# switches.net
KiCad netlist of a schematic drawn in Altium Designer
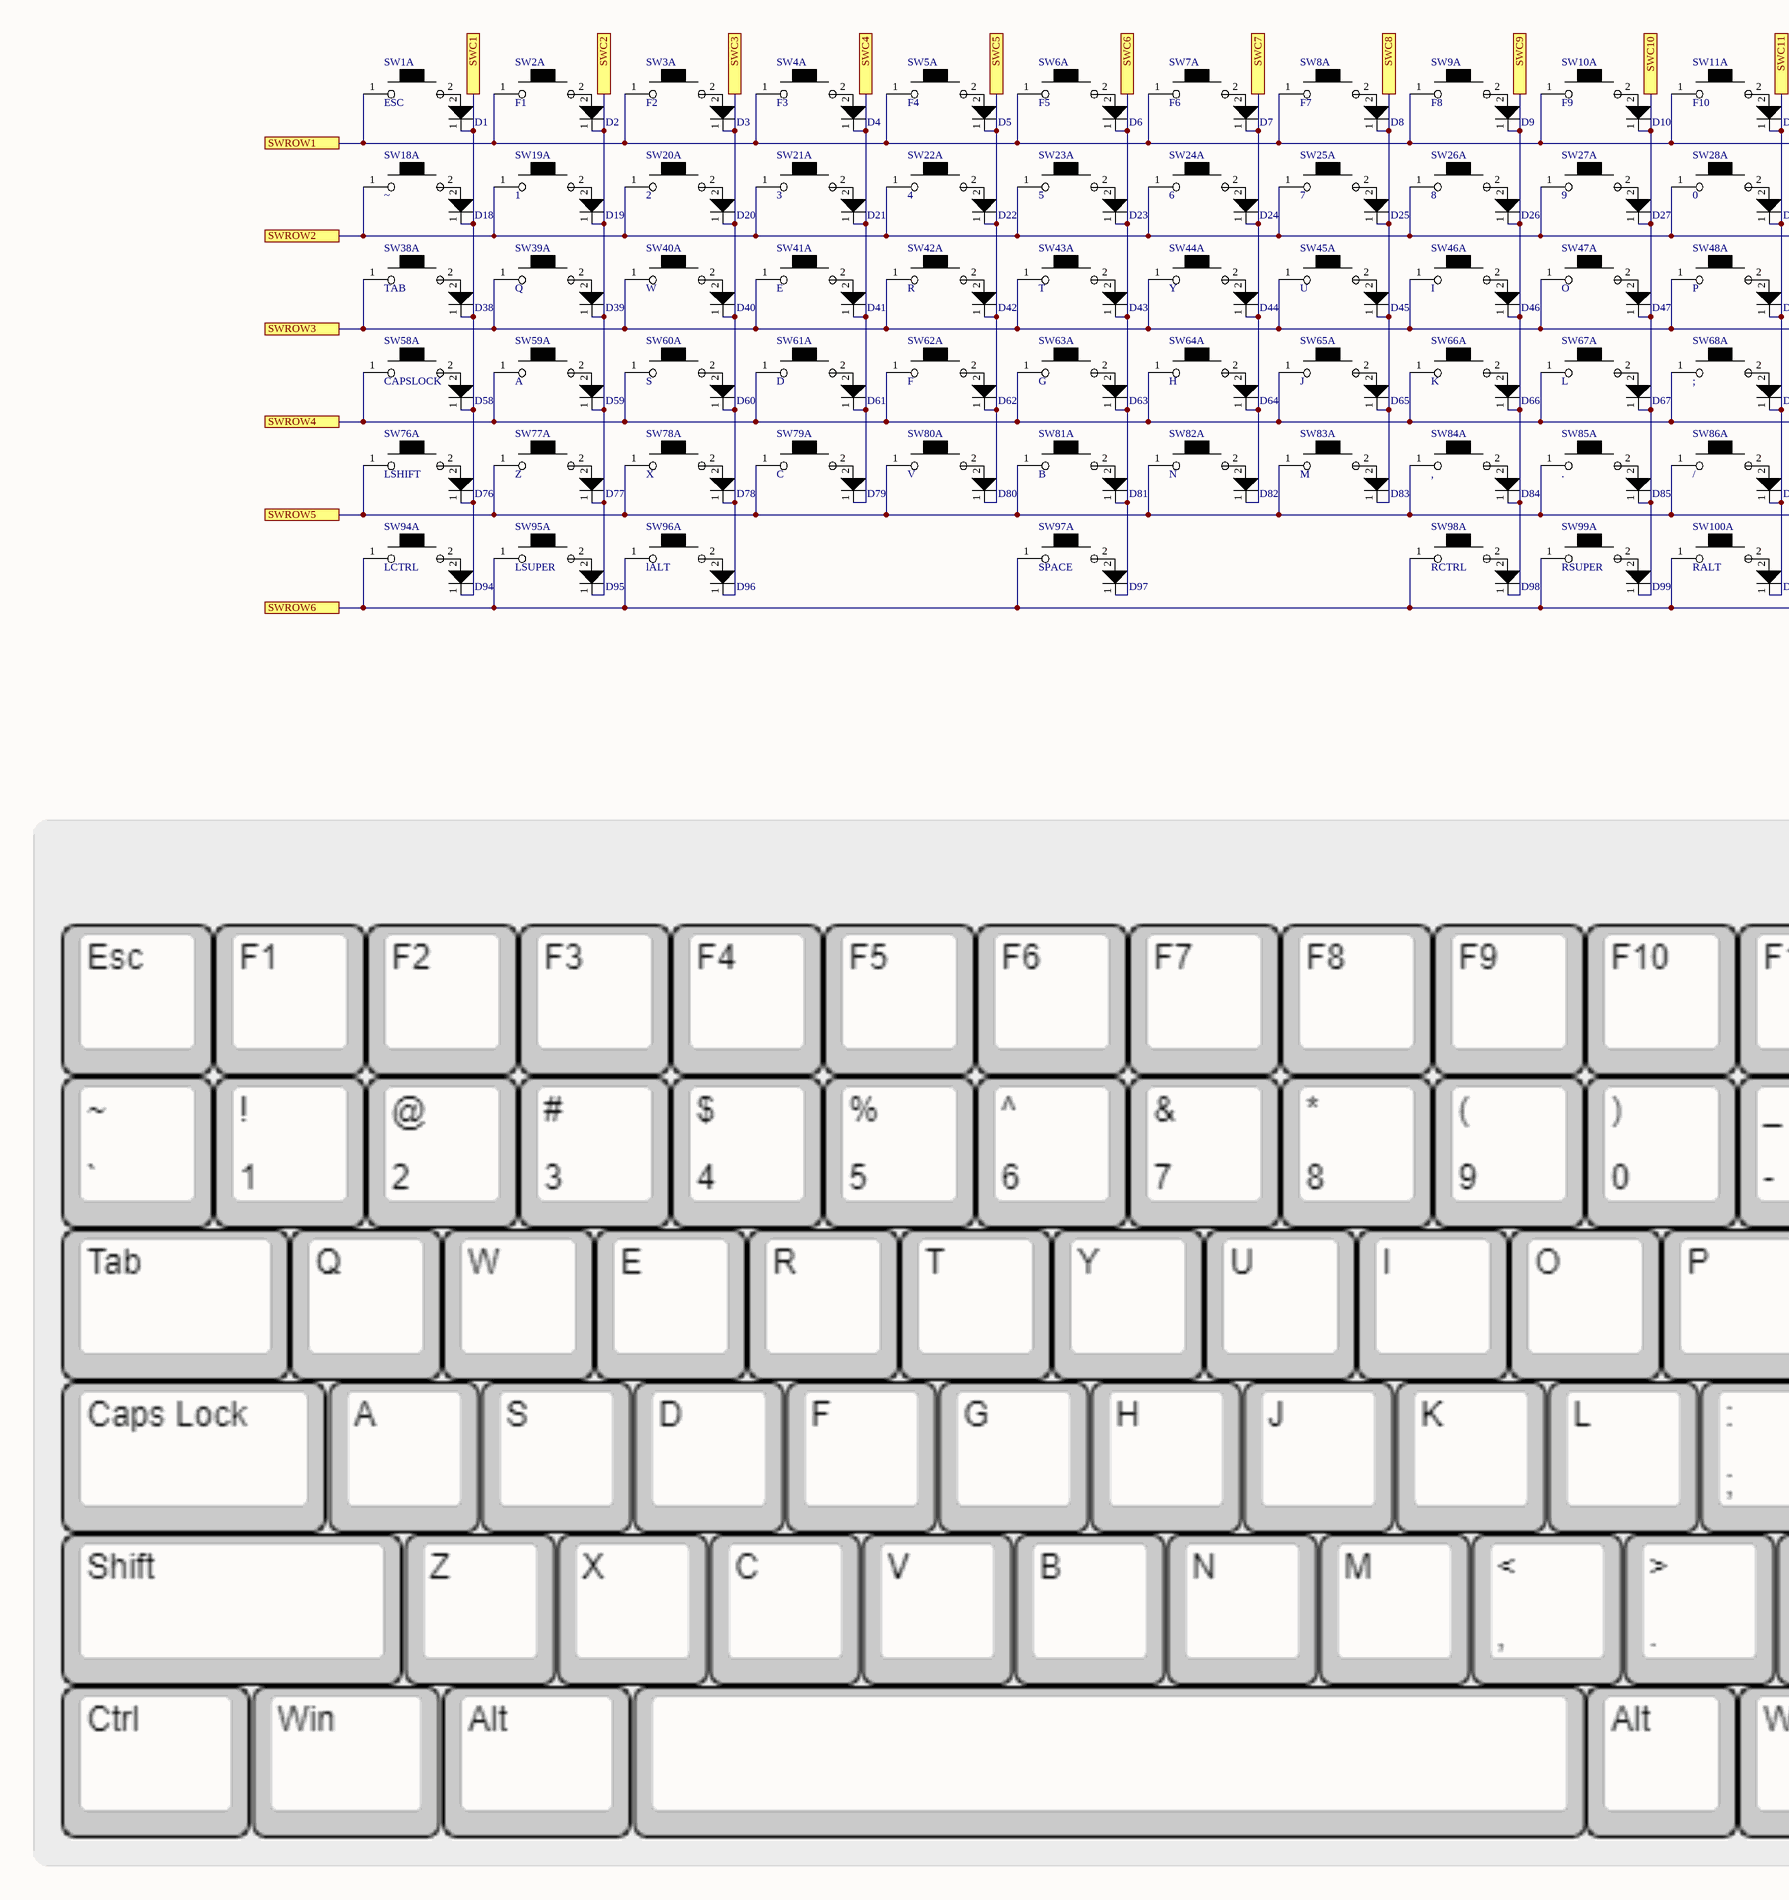
[diagram p0: switches.SchDoc, left]
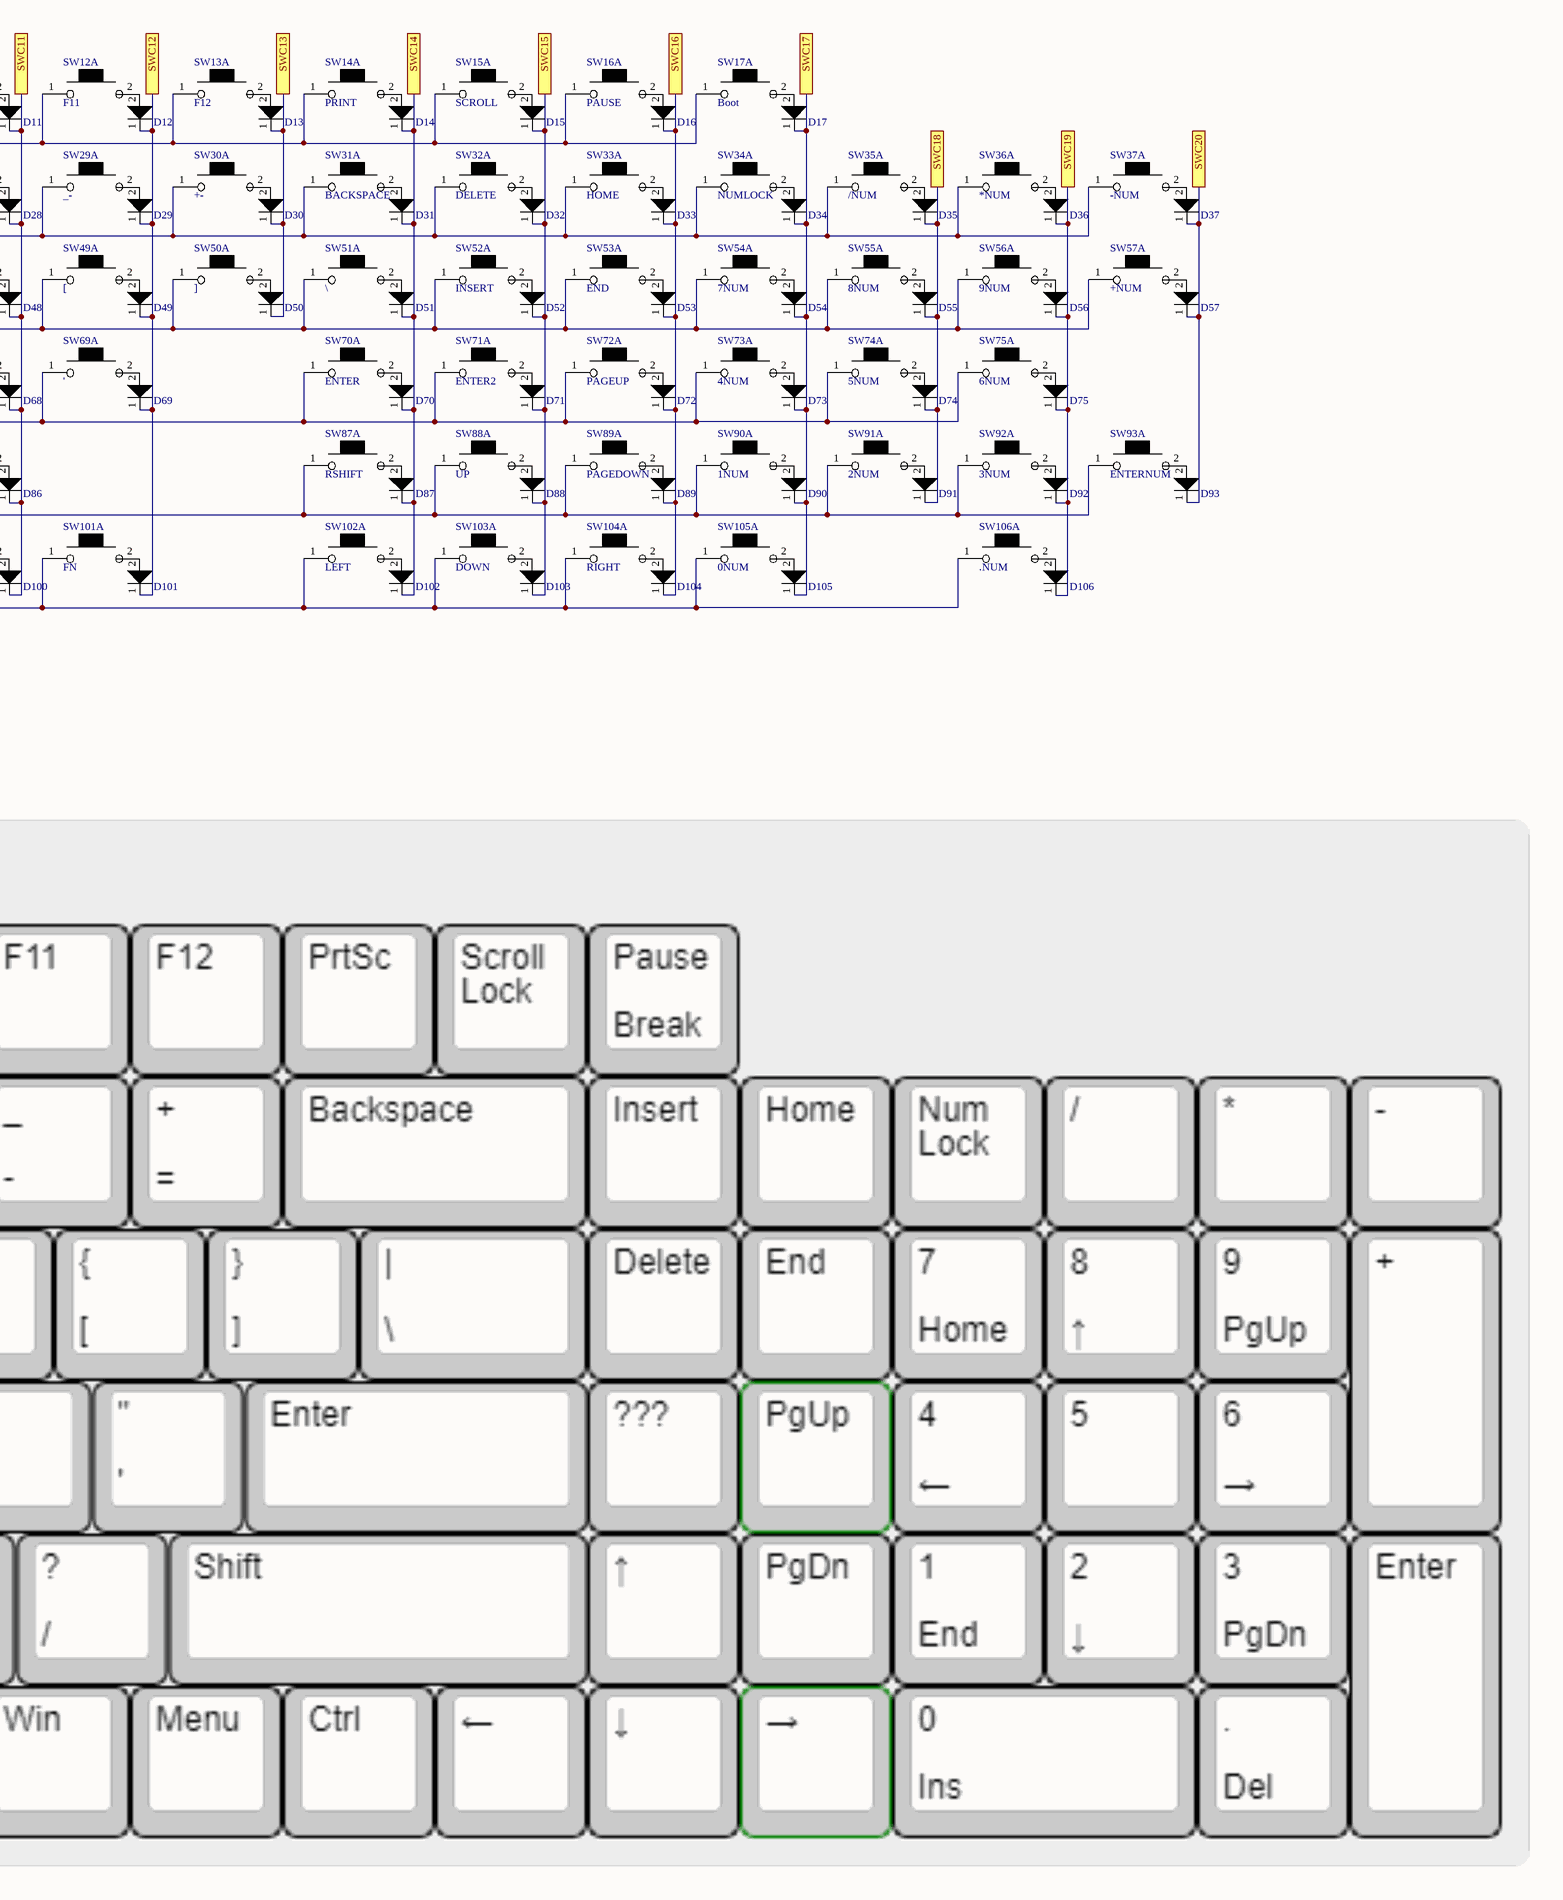
[diagram p1: switches.SchDoc, right]

(export (version "E")
  (design (tool "Eeschema 10.0.6"))
  (components
    (comp (ref "D1") (value "1N4148WTR") (footprint "SOD-123") (libsource (lib "General") (part "1N4148WTR")))
    (comp (ref "D2") (value "1N4148WTR") (footprint "SOD-123") (libsource (lib "General") (part "1N4148WTR")))
    (comp (ref "D3") (value "1N4148WTR") (footprint "SOD-123") (libsource (lib "General") (part "1N4148WTR")))
    (comp (ref "D4") (value "1N4148WTR") (footprint "SOD-123") (libsource (lib "General") (part "1N4148WTR")))
    (comp (ref "D5") (value "1N4148WTR") (footprint "SOD-123") (libsource (lib "General") (part "1N4148WTR")))
    (comp (ref "D6") (value "1N4148WTR") (footprint "SOD-123") (libsource (lib "General") (part "1N4148WTR")))
    (comp (ref "D7") (value "1N4148WTR") (footprint "SOD-123") (libsource (lib "General") (part "1N4148WTR")))
    (comp (ref "D8") (value "1N4148WTR") (footprint "SOD-123") (libsource (lib "General") (part "1N4148WTR")))
    (comp (ref "D9") (value "1N4148WTR") (footprint "SOD-123") (libsource (lib "General") (part "1N4148WTR")))
    (comp (ref "D10")
      (value "1N4148WTR")
      (footprint "SOD-123")
      (libsource (lib "General") (part "1N4148WTR"))
    )
    (comp (ref "D11")
      (value "1N4148WTR")
      (footprint "SOD-123")
      (libsource (lib "General") (part "1N4148WTR"))
    )
    (comp (ref "D12")
      (value "1N4148WTR")
      (footprint "SOD-123")
      (libsource (lib "General") (part "1N4148WTR"))
    )
    (comp (ref "D13")
      (value "1N4148WTR")
      (footprint "SOD-123")
      (libsource (lib "General") (part "1N4148WTR"))
    )
    (comp (ref "D14")
      (value "1N4148WTR")
      (footprint "SOD-123")
      (libsource (lib "General") (part "1N4148WTR"))
    )
    (comp (ref "D15")
      (value "1N4148WTR")
      (footprint "SOD-123")
      (libsource (lib "General") (part "1N4148WTR"))
    )
    (comp (ref "D16")
      (value "1N4148WTR")
      (footprint "SOD-123")
      (libsource (lib "General") (part "1N4148WTR"))
    )
    (comp (ref "D17")
      (value "1N4148WTR")
      (footprint "SOD-123")
      (libsource (lib "General") (part "1N4148WTR"))
    )
    (comp (ref "D18")
      (value "1N4148WTR")
      (footprint "SOD-123")
      (libsource (lib "General") (part "1N4148WTR"))
    )
    (comp (ref "D19")
      (value "1N4148WTR")
      (footprint "SOD-123")
      (libsource (lib "General") (part "1N4148WTR"))
    )
    (comp (ref "D20")
      (value "1N4148WTR")
      (footprint "SOD-123")
      (libsource (lib "General") (part "1N4148WTR"))
    )
    (comp (ref "D21")
      (value "1N4148WTR")
      (footprint "SOD-123")
      (libsource (lib "General") (part "1N4148WTR"))
    )
    (comp (ref "D22")
      (value "1N4148WTR")
      (footprint "SOD-123")
      (libsource (lib "General") (part "1N4148WTR"))
    )
    (comp (ref "D23")
      (value "1N4148WTR")
      (footprint "SOD-123")
      (libsource (lib "General") (part "1N4148WTR"))
    )
    (comp (ref "D24")
      (value "1N4148WTR")
      (footprint "SOD-123")
      (libsource (lib "General") (part "1N4148WTR"))
    )
    (comp (ref "D25")
      (value "1N4148WTR")
      (footprint "SOD-123")
      (libsource (lib "General") (part "1N4148WTR"))
    )
    (comp (ref "D26")
      (value "1N4148WTR")
      (footprint "SOD-123")
      (libsource (lib "General") (part "1N4148WTR"))
    )
    (comp (ref "D27")
      (value "1N4148WTR")
      (footprint "SOD-123")
      (libsource (lib "General") (part "1N4148WTR"))
    )
    (comp (ref "D28")
      (value "1N4148WTR")
      (footprint "SOD-123")
      (libsource (lib "General") (part "1N4148WTR"))
    )
    (comp (ref "D29")
      (value "1N4148WTR")
      (footprint "SOD-123")
      (libsource (lib "General") (part "1N4148WTR"))
    )
    (comp (ref "D30")
      (value "1N4148WTR")
      (footprint "SOD-123")
      (libsource (lib "General") (part "1N4148WTR"))
    )
    (comp (ref "D31")
      (value "1N4148WTR")
      (footprint "SOD-123")
      (libsource (lib "General") (part "1N4148WTR"))
    )
    (comp (ref "D32")
      (value "1N4148WTR")
      (footprint "SOD-123")
      (libsource (lib "General") (part "1N4148WTR"))
    )
    (comp (ref "D33")
      (value "1N4148WTR")
      (footprint "SOD-123")
      (libsource (lib "General") (part "1N4148WTR"))
    )
    (comp (ref "D34")
      (value "1N4148WTR")
      (footprint "SOD-123")
      (libsource (lib "General") (part "1N4148WTR"))
    )
    (comp (ref "D35")
      (value "1N4148WTR")
      (footprint "SOD-123")
      (libsource (lib "General") (part "1N4148WTR"))
    )
    (comp (ref "D36")
      (value "1N4148WTR")
      (footprint "SOD-123")
      (libsource (lib "General") (part "1N4148WTR"))
    )
    (comp (ref "D37")
      (value "1N4148WTR")
      (footprint "SOD-123")
      (libsource (lib "General") (part "1N4148WTR"))
    )
    (comp (ref "D38")
      (value "1N4148WTR")
      (footprint "SOD-123")
      (libsource (lib "General") (part "1N4148WTR"))
    )
    (comp (ref "D39")
      (value "1N4148WTR")
      (footprint "SOD-123")
      (libsource (lib "General") (part "1N4148WTR"))
    )
    (comp (ref "D40")
      (value "1N4148WTR")
      (footprint "SOD-123")
      (libsource (lib "General") (part "1N4148WTR"))
    )
    (comp (ref "D41")
      (value "1N4148WTR")
      (footprint "SOD-123")
      (libsource (lib "General") (part "1N4148WTR"))
    )
    (comp (ref "D42")
      (value "1N4148WTR")
      (footprint "SOD-123")
      (libsource (lib "General") (part "1N4148WTR"))
    )
    (comp (ref "D43")
      (value "1N4148WTR")
      (footprint "SOD-123")
      (libsource (lib "General") (part "1N4148WTR"))
    )
    (comp (ref "D44")
      (value "1N4148WTR")
      (footprint "SOD-123")
      (libsource (lib "General") (part "1N4148WTR"))
    )
    (comp (ref "D45")
      (value "1N4148WTR")
      (footprint "SOD-123")
      (libsource (lib "General") (part "1N4148WTR"))
    )
    (comp (ref "D46")
      (value "1N4148WTR")
      (footprint "SOD-123")
      (libsource (lib "General") (part "1N4148WTR"))
    )
    (comp (ref "D47")
      (value "1N4148WTR")
      (footprint "SOD-123")
      (libsource (lib "General") (part "1N4148WTR"))
    )
    (comp (ref "D48")
      (value "1N4148WTR")
      (footprint "SOD-123")
      (libsource (lib "General") (part "1N4148WTR"))
    )
    (comp (ref "D49")
      (value "1N4148WTR")
      (footprint "SOD-123")
      (libsource (lib "General") (part "1N4148WTR"))
    )
    (comp (ref "D50")
      (value "1N4148WTR")
      (footprint "SOD-123")
      (libsource (lib "General") (part "1N4148WTR"))
    )
    (comp (ref "D51")
      (value "1N4148WTR")
      (footprint "SOD-123")
      (libsource (lib "General") (part "1N4148WTR"))
    )
    (comp (ref "D52")
      (value "1N4148WTR")
      (footprint "SOD-123")
      (libsource (lib "General") (part "1N4148WTR"))
    )
    (comp (ref "D53")
      (value "1N4148WTR")
      (footprint "SOD-123")
      (libsource (lib "General") (part "1N4148WTR"))
    )
    (comp (ref "D54")
      (value "1N4148WTR")
      (footprint "SOD-123")
      (libsource (lib "General") (part "1N4148WTR"))
    )
    (comp (ref "D55")
      (value "1N4148WTR")
      (footprint "SOD-123")
      (libsource (lib "General") (part "1N4148WTR"))
    )
    (comp (ref "D56")
      (value "1N4148WTR")
      (footprint "SOD-123")
      (libsource (lib "General") (part "1N4148WTR"))
    )
    (comp (ref "D57")
      (value "1N4148WTR")
      (footprint "SOD-123")
      (libsource (lib "General") (part "1N4148WTR"))
    )
    (comp (ref "D58")
      (value "1N4148WTR")
      (footprint "SOD-123")
      (libsource (lib "General") (part "1N4148WTR"))
    )
    (comp (ref "D59")
      (value "1N4148WTR")
      (footprint "SOD-123")
      (libsource (lib "General") (part "1N4148WTR"))
    )
    (comp (ref "D60")
      (value "1N4148WTR")
      (footprint "SOD-123")
      (libsource (lib "General") (part "1N4148WTR"))
    )
    (comp (ref "D61")
      (value "1N4148WTR")
      (footprint "SOD-123")
      (libsource (lib "General") (part "1N4148WTR"))
    )
    (comp (ref "D62")
      (value "1N4148WTR")
      (footprint "SOD-123")
      (libsource (lib "General") (part "1N4148WTR"))
    )
    (comp (ref "D63")
      (value "1N4148WTR")
      (footprint "SOD-123")
      (libsource (lib "General") (part "1N4148WTR"))
    )
    (comp (ref "D64")
      (value "1N4148WTR")
      (footprint "SOD-123")
      (libsource (lib "General") (part "1N4148WTR"))
    )
    (comp (ref "D65")
      (value "1N4148WTR")
      (footprint "SOD-123")
      (libsource (lib "General") (part "1N4148WTR"))
    )
    (comp (ref "D66")
      (value "1N4148WTR")
      (footprint "SOD-123")
      (libsource (lib "General") (part "1N4148WTR"))
    )
    (comp (ref "D67")
      (value "1N4148WTR")
      (footprint "SOD-123")
      (libsource (lib "General") (part "1N4148WTR"))
    )
    (comp (ref "D68")
      (value "1N4148WTR")
      (footprint "SOD-123")
      (libsource (lib "General") (part "1N4148WTR"))
    )
    (comp (ref "D69")
      (value "1N4148WTR")
      (footprint "SOD-123")
      (libsource (lib "General") (part "1N4148WTR"))
    )
    (comp (ref "D70")
      (value "1N4148WTR")
      (footprint "SOD-123")
      (libsource (lib "General") (part "1N4148WTR"))
    )
    (comp (ref "D71")
      (value "1N4148WTR")
      (footprint "SOD-123")
      (libsource (lib "General") (part "1N4148WTR"))
    )
    (comp (ref "D72")
      (value "1N4148WTR")
      (footprint "SOD-123")
      (libsource (lib "General") (part "1N4148WTR"))
    )
    (comp (ref "D73")
      (value "1N4148WTR")
      (footprint "SOD-123")
      (libsource (lib "General") (part "1N4148WTR"))
    )
    (comp (ref "D74")
      (value "1N4148WTR")
      (footprint "SOD-123")
      (libsource (lib "General") (part "1N4148WTR"))
    )
    (comp (ref "D75")
      (value "1N4148WTR")
      (footprint "SOD-123")
      (libsource (lib "General") (part "1N4148WTR"))
    )
    (comp (ref "D76")
      (value "1N4148WTR")
      (footprint "SOD-123")
      (libsource (lib "General") (part "1N4148WTR"))
    )
    (comp (ref "D77")
      (value "1N4148WTR")
      (footprint "SOD-123")
      (libsource (lib "General") (part "1N4148WTR"))
    )
    (comp (ref "D78")
      (value "1N4148WTR")
      (footprint "SOD-123")
      (libsource (lib "General") (part "1N4148WTR"))
    )
    (comp (ref "D79")
      (value "1N4148WTR")
      (footprint "SOD-123")
      (libsource (lib "General") (part "1N4148WTR"))
    )
    (comp (ref "D80")
      (value "1N4148WTR")
      (footprint "SOD-123")
      (libsource (lib "General") (part "1N4148WTR"))
    )
    (comp (ref "D81")
      (value "1N4148WTR")
      (footprint "SOD-123")
      (libsource (lib "General") (part "1N4148WTR"))
    )
    (comp (ref "D82")
      (value "1N4148WTR")
      (footprint "SOD-123")
      (libsource (lib "General") (part "1N4148WTR"))
    )
    (comp (ref "D83")
      (value "1N4148WTR")
      (footprint "SOD-123")
      (libsource (lib "General") (part "1N4148WTR"))
    )
    (comp (ref "D84")
      (value "1N4148WTR")
      (footprint "SOD-123")
      (libsource (lib "General") (part "1N4148WTR"))
    )
    (comp (ref "D85")
      (value "1N4148WTR")
      (footprint "SOD-123")
      (libsource (lib "General") (part "1N4148WTR"))
    )
    (comp (ref "D86")
      (value "1N4148WTR")
      (footprint "SOD-123")
      (libsource (lib "General") (part "1N4148WTR"))
    )
    (comp (ref "D87")
      (value "1N4148WTR")
      (footprint "SOD-123")
      (libsource (lib "General") (part "1N4148WTR"))
    )
    (comp (ref "D88")
      (value "1N4148WTR")
      (footprint "SOD-123")
      (libsource (lib "General") (part "1N4148WTR"))
    )
    (comp (ref "D89")
      (value "1N4148WTR")
      (footprint "SOD-123")
      (libsource (lib "General") (part "1N4148WTR"))
    )
    (comp (ref "D90")
      (value "1N4148WTR")
      (footprint "SOD-123")
      (libsource (lib "General") (part "1N4148WTR"))
    )
    (comp (ref "D91")
      (value "1N4148WTR")
      (footprint "SOD-123")
      (libsource (lib "General") (part "1N4148WTR"))
    )
    (comp (ref "D92")
      (value "1N4148WTR")
      (footprint "SOD-123")
      (libsource (lib "General") (part "1N4148WTR"))
    )
    (comp (ref "D93")
      (value "1N4148WTR")
      (footprint "SOD-123")
      (libsource (lib "General") (part "1N4148WTR"))
    )
    (comp (ref "D94")
      (value "1N4148WTR")
      (footprint "SOD-123")
      (libsource (lib "General") (part "1N4148WTR"))
    )
    (comp (ref "D95")
      (value "1N4148WTR")
      (footprint "SOD-123")
      (libsource (lib "General") (part "1N4148WTR"))
    )
    (comp (ref "D96")
      (value "1N4148WTR")
      (footprint "SOD-123")
      (libsource (lib "General") (part "1N4148WTR"))
    )
    (comp (ref "D97")
      (value "1N4148WTR")
      (footprint "SOD-123")
      (libsource (lib "General") (part "1N4148WTR"))
    )
    (comp (ref "D98")
      (value "1N4148WTR")
      (footprint "SOD-123")
      (libsource (lib "General") (part "1N4148WTR"))
    )
    (comp (ref "D99")
      (value "1N4148WTR")
      (footprint "SOD-123")
      (libsource (lib "General") (part "1N4148WTR"))
    )
    (comp (ref "D100")
      (value "1N4148WTR")
      (footprint "SOD-123")
      (libsource (lib "General") (part "1N4148WTR"))
    )
    (comp (ref "D101")
      (value "1N4148WTR")
      (footprint "SOD-123")
      (libsource (lib "General") (part "1N4148WTR"))
    )
    (comp (ref "D102")
      (value "1N4148WTR")
      (footprint "SOD-123")
      (libsource (lib "General") (part "1N4148WTR"))
    )
    (comp (ref "D103")
      (value "1N4148WTR")
      (footprint "SOD-123")
      (libsource (lib "General") (part "1N4148WTR"))
    )
    (comp (ref "D104")
      (value "1N4148WTR")
      (footprint "SOD-123")
      (libsource (lib "General") (part "1N4148WTR"))
    )
    (comp (ref "D105")
      (value "1N4148WTR")
      (footprint "SOD-123")
      (libsource (lib "General") (part "1N4148WTR"))
    )
    (comp (ref "D106")
      (value "1N4148WTR")
      (footprint "SOD-123")
      (libsource (lib "General") (part "1N4148WTR"))
    )
    (comp (ref "SW1")
      (value "ESC")
      (footprint "SWITCH_U1_W_LED")
      (libsource (lib "General") (part "MX_SWITCH_SINGLE_W_SMD_LED"))
    )
    (comp (ref "SW2")
      (value "F1")
      (footprint "SWITCH_U1_W_LED")
      (libsource (lib "General") (part "MX_SWITCH_SINGLE_W_SMD_LED"))
    )
    (comp (ref "SW3")
      (value "F2")
      (footprint "SWITCH_U1_W_LED")
      (libsource (lib "General") (part "MX_SWITCH_SINGLE_W_SMD_LED"))
    )
    (comp (ref "SW4")
      (value "F3")
      (footprint "SWITCH_U1_W_LED")
      (libsource (lib "General") (part "MX_SWITCH_SINGLE_W_SMD_LED"))
    )
    (comp (ref "SW5")
      (value "F4")
      (footprint "SWITCH_U1_W_LED")
      (libsource (lib "General") (part "MX_SWITCH_SINGLE_W_SMD_LED"))
    )
    (comp (ref "SW6")
      (value "F5")
      (footprint "SWITCH_U1_W_LED")
      (libsource (lib "General") (part "MX_SWITCH_SINGLE_W_SMD_LED"))
    )
    (comp (ref "SW7")
      (value "F6")
      (footprint "SWITCH_U1_W_LED")
      (libsource (lib "General") (part "MX_SWITCH_SINGLE_W_SMD_LED"))
    )
    (comp (ref "SW8")
      (value "F7")
      (footprint "SWITCH_U1_W_LED")
      (libsource (lib "General") (part "MX_SWITCH_SINGLE_W_SMD_LED"))
    )
    (comp (ref "SW9")
      (value "F8")
      (footprint "SWITCH_U1_W_LED")
      (libsource (lib "General") (part "MX_SWITCH_SINGLE_W_SMD_LED"))
    )
    (comp (ref "SW10")
      (value "F9")
      (footprint "SWITCH_U1_W_LED")
      (libsource (lib "General") (part "MX_SWITCH_SINGLE_W_SMD_LED"))
    )
    (comp (ref "SW11")
      (value "F10")
      (footprint "SWITCH_U1_W_LED")
      (libsource (lib "General") (part "MX_SWITCH_SINGLE_W_SMD_LED"))
    )
    (comp (ref "SW12")
      (value "F11")
      (footprint "SWITCH_U1_W_LED")
      (libsource (lib "General") (part "MX_SWITCH_SINGLE_W_SMD_LED"))
    )
    (comp (ref "SW13")
      (value "F12")
      (footprint "SWITCH_U1_W_LED")
      (libsource (lib "General") (part "MX_SWITCH_SINGLE_W_SMD_LED"))
    )
    (comp (ref "SW14")
      (value "PRINT")
      (footprint "SWITCH_U1_W_LED")
      (libsource (lib "General") (part "MX_SWITCH_SINGLE_W_SMD_LED"))
    )
    (comp (ref "SW15")
      (value "SCROLL")
      (footprint "SWITCH_U1_W_LED")
      (libsource (lib "General") (part "MX_SWITCH_SINGLE_W_SMD_LED"))
    )
    (comp (ref "SW16")
      (value "PAUSE")
      (footprint "SWITCH_U1_W_LED")
      (libsource (lib "General") (part "MX_SWITCH_SINGLE_W_SMD_LED"))
    )
    (comp (ref "SW17")
      (value "Boot")
      (footprint "SWITCH_U1_W_LED")
      (libsource (lib "General") (part "MX_SWITCH_SINGLE_W_SMD_LED"))
    )
    (comp (ref "SW18")
      (value "~")
      (footprint "SWITCH_U1_W_LED")
      (libsource (lib "General") (part "MX_SWITCH_SINGLE_W_SMD_LED"))
    )
    (comp (ref "SW19")
      (value "1")
      (footprint "SWITCH_U1_W_LED")
      (libsource (lib "General") (part "MX_SWITCH_SINGLE_W_SMD_LED"))
    )
    (comp (ref "SW20")
      (value "2")
      (footprint "SWITCH_U1_W_LED")
      (libsource (lib "General") (part "MX_SWITCH_SINGLE_W_SMD_LED"))
    )
    (comp (ref "SW21")
      (value "3")
      (footprint "SWITCH_U1_W_LED")
      (libsource (lib "General") (part "MX_SWITCH_SINGLE_W_SMD_LED"))
    )
    (comp (ref "SW22")
      (value "4")
      (footprint "SWITCH_U1_W_LED")
      (libsource (lib "General") (part "MX_SWITCH_SINGLE_W_SMD_LED"))
    )
    (comp (ref "SW23")
      (value "5")
      (footprint "SWITCH_U1_W_LED")
      (libsource (lib "General") (part "MX_SWITCH_SINGLE_W_SMD_LED"))
    )
    (comp (ref "SW24")
      (value "6")
      (footprint "SWITCH_U1_W_LED")
      (libsource (lib "General") (part "MX_SWITCH_SINGLE_W_SMD_LED"))
    )
    (comp (ref "SW25")
      (value "7")
      (footprint "SWITCH_U1_W_LED")
      (libsource (lib "General") (part "MX_SWITCH_SINGLE_W_SMD_LED"))
    )
    (comp (ref "SW26")
      (value "8")
      (footprint "SWITCH_U1_W_LED")
      (libsource (lib "General") (part "MX_SWITCH_SINGLE_W_SMD_LED"))
    )
    (comp (ref "SW27")
      (value "9")
      (footprint "SWITCH_U1_W_LED")
      (libsource (lib "General") (part "MX_SWITCH_SINGLE_W_SMD_LED"))
    )
    (comp (ref "SW28")
      (value "0")
      (footprint "SWITCH_U1_W_LED")
      (libsource (lib "General") (part "MX_SWITCH_SINGLE_W_SMD_LED"))
    )
    (comp (ref "SW29")
      (value "_-")
      (footprint "SWITCH_U1_W_LED")
      (libsource (lib "General") (part "MX_SWITCH_SINGLE_W_SMD_LED"))
    )
    (comp (ref "SW30")
      (value "+-")
      (footprint "SWITCH_U1_W_LED")
      (libsource (lib "General") (part "MX_SWITCH_SINGLE_W_SMD_LED"))
    )
    (comp (ref "SW31")
      (value "BACKSPACE")
      (footprint "SWITCH_U2_W_LED")
      (libsource (lib "General") (part "MX_SWITCH_SINGLE_W_SMD_LED"))
    )
    (comp (ref "SW32")
      (value "DELETE")
      (footprint "SWITCH_U1_W_LED")
      (libsource (lib "General") (part "MX_SWITCH_SINGLE_W_SMD_LED"))
    )
    (comp (ref "SW33")
      (value "HOME")
      (footprint "SWITCH_U1_W_LED")
      (libsource (lib "General") (part "MX_SWITCH_SINGLE_W_SMD_LED"))
    )
    (comp (ref "SW34")
      (value "NUMLOCK")
      (footprint "SWITCH_U1_W_LED")
      (libsource (lib "General") (part "MX_SWITCH_SINGLE_W_SMD_LED"))
    )
    (comp (ref "SW35")
      (value "/NUM")
      (footprint "SWITCH_U1_W_LED")
      (libsource (lib "General") (part "MX_SWITCH_SINGLE_W_SMD_LED"))
    )
    (comp (ref "SW36")
      (value "*NUM")
      (footprint "SWITCH_U1_W_LED")
      (libsource (lib "General") (part "MX_SWITCH_SINGLE_W_SMD_LED"))
    )
    (comp (ref "SW37")
      (value "-NUM")
      (footprint "SWITCH_U1_W_LED")
      (libsource (lib "General") (part "MX_SWITCH_SINGLE_W_SMD_LED"))
    )
    (comp (ref "SW38")
      (value "TAB")
      (footprint "SWITCH_U1.50_W_LED")
      (libsource (lib "General") (part "MX_SWITCH_SINGLE_W_SMD_LED"))
    )
    (comp (ref "SW39")
      (value "Q")
      (footprint "SWITCH_U1_W_LED")
      (libsource (lib "General") (part "MX_SWITCH_SINGLE_W_SMD_LED"))
    )
    (comp (ref "SW40")
      (value "W")
      (footprint "SWITCH_U1_W_LED")
      (libsource (lib "General") (part "MX_SWITCH_SINGLE_W_SMD_LED"))
    )
    (comp (ref "SW41")
      (value "E")
      (footprint "SWITCH_U1_W_LED")
      (libsource (lib "General") (part "MX_SWITCH_SINGLE_W_SMD_LED"))
    )
    (comp (ref "SW42")
      (value "R")
      (footprint "SWITCH_U1_W_LED")
      (libsource (lib "General") (part "MX_SWITCH_SINGLE_W_SMD_LED"))
    )
    (comp (ref "SW43")
      (value "T")
      (footprint "SWITCH_U1_W_LED")
      (libsource (lib "General") (part "MX_SWITCH_SINGLE_W_SMD_LED"))
    )
    (comp (ref "SW44")
      (value "Y")
      (footprint "SWITCH_U1_W_LED")
      (libsource (lib "General") (part "MX_SWITCH_SINGLE_W_SMD_LED"))
    )
    (comp (ref "SW45")
      (value "U")
      (footprint "SWITCH_U1_W_LED")
      (libsource (lib "General") (part "MX_SWITCH_SINGLE_W_SMD_LED"))
    )
    (comp (ref "SW46")
      (value "I")
      (footprint "SWITCH_U1_W_LED")
      (libsource (lib "General") (part "MX_SWITCH_SINGLE_W_SMD_LED"))
    )
    (comp (ref "SW47")
      (value "O")
      (footprint "SWITCH_U1_W_LED")
      (libsource (lib "General") (part "MX_SWITCH_SINGLE_W_SMD_LED"))
    )
    (comp (ref "SW48")
      (value "P")
      (footprint "SWITCH_U1_W_LED")
      (libsource (lib "General") (part "MX_SWITCH_SINGLE_W_SMD_LED"))
    )
    (comp (ref "SW49")
      (value "[")
      (footprint "SWITCH_U1_W_LED")
      (libsource (lib "General") (part "MX_SWITCH_SINGLE_W_SMD_LED"))
    )
    (comp (ref "SW50")
      (value "]")
      (footprint "SWITCH_U1_W_LED")
      (libsource (lib "General") (part "MX_SWITCH_SINGLE_W_SMD_LED"))
    )
    (comp (ref "SW51")
      (value "\\")
      (footprint "SWITCH_U1.50_W_LED")
      (libsource (lib "General") (part "MX_SWITCH_SINGLE_W_SMD_LED"))
    )
    (comp (ref "SW52")
      (value "INSERT")
      (footprint "SWITCH_U1_W_LED")
      (libsource (lib "General") (part "MX_SWITCH_SINGLE_W_SMD_LED"))
    )
    (comp (ref "SW53")
      (value "END")
      (footprint "SWITCH_U1_W_LED")
      (libsource (lib "General") (part "MX_SWITCH_SINGLE_W_SMD_LED"))
    )
    (comp (ref "SW54")
      (value "7NUM")
      (footprint "SWITCH_U1_W_LED")
      (libsource (lib "General") (part "MX_SWITCH_SINGLE_W_SMD_LED"))
    )
    (comp (ref "SW55")
      (value "8NUM")
      (footprint "SWITCH_U1_W_LED")
      (libsource (lib "General") (part "MX_SWITCH_SINGLE_W_SMD_LED"))
    )
    (comp (ref "SW56")
      (value "9NUM")
      (footprint "SWITCH_U1_W_LED")
      (libsource (lib "General") (part "MX_SWITCH_SINGLE_W_SMD_LED"))
    )
    (comp (ref "SW57")
      (value "+NUM")
      (footprint "SWITCH_U2_W_LED - vert")
      (libsource (lib "General") (part "MX_SWITCH_SINGLE_W_SMD_LED"))
    )
    (comp (ref "SW58")
      (value "CAPSLOCK")
      (footprint "SWITCH_U1.75_W_LED")
      (libsource (lib "General") (part "MX_SWITCH_SINGLE_W_SMD_LED"))
    )
    (comp (ref "SW59")
      (value "A")
      (footprint "SWITCH_U1_W_LED")
      (libsource (lib "General") (part "MX_SWITCH_SINGLE_W_SMD_LED"))
    )
    (comp (ref "SW60")
      (value "S")
      (footprint "SWITCH_U1_W_LED")
      (libsource (lib "General") (part "MX_SWITCH_SINGLE_W_SMD_LED"))
    )
    (comp (ref "SW61")
      (value "D")
      (footprint "SWITCH_U1_W_LED")
      (libsource (lib "General") (part "MX_SWITCH_SINGLE_W_SMD_LED"))
    )
    (comp (ref "SW62")
      (value "F")
      (footprint "SWITCH_U1_W_LED")
      (libsource (lib "General") (part "MX_SWITCH_SINGLE_W_SMD_LED"))
    )
    (comp (ref "SW63")
      (value "G")
      (footprint "SWITCH_U1_W_LED")
      (libsource (lib "General") (part "MX_SWITCH_SINGLE_W_SMD_LED"))
    )
    (comp (ref "SW64")
      (value "H")
      (footprint "SWITCH_U1_W_LED")
      (libsource (lib "General") (part "MX_SWITCH_SINGLE_W_SMD_LED"))
    )
    (comp (ref "SW65")
      (value "J")
      (footprint "SWITCH_U1_W_LED")
      (libsource (lib "General") (part "MX_SWITCH_SINGLE_W_SMD_LED"))
    )
    (comp (ref "SW66")
      (value "K")
      (footprint "SWITCH_U1_W_LED")
      (libsource (lib "General") (part "MX_SWITCH_SINGLE_W_SMD_LED"))
    )
    (comp (ref "SW67")
      (value "L")
      (footprint "SWITCH_U1_W_LED")
      (libsource (lib "General") (part "MX_SWITCH_SINGLE_W_SMD_LED"))
    )
    (comp (ref "SW68")
      (value ";")
      (footprint "SWITCH_U1_W_LED")
      (libsource (lib "General") (part "MX_SWITCH_SINGLE_W_SMD_LED"))
    )
    (comp (ref "SW69")
      (value "'")
      (footprint "SWITCH_U1_W_LED")
      (libsource (lib "General") (part "MX_SWITCH_SINGLE_W_SMD_LED"))
    )
    (comp (ref "SW70")
      (value "ENTER")
      (footprint "SWITCH_U2.25_W_LED")
      (libsource (lib "General") (part "MX_SWITCH_SINGLE_W_SMD_LED"))
    )
    (comp (ref "SW71")
      (value "ENTER2")
      (footprint "SWITCH_U1_W_LED")
      (libsource (lib "General") (part "MX_SWITCH_SINGLE_W_SMD_LED"))
    )
    (comp (ref "SW72")
      (value "PAGEUP")
      (footprint "SWITCH_U1_W_LED")
      (libsource (lib "General") (part "MX_SWITCH_SINGLE_W_SMD_LED"))
    )
    (comp (ref "SW73")
      (value "4NUM")
      (footprint "SWITCH_U1_W_LED")
      (libsource (lib "General") (part "MX_SWITCH_SINGLE_W_SMD_LED"))
    )
    (comp (ref "SW74")
      (value "5NUM")
      (footprint "SWITCH_U1_W_LED")
      (libsource (lib "General") (part "MX_SWITCH_SINGLE_W_SMD_LED"))
    )
    (comp (ref "SW75")
      (value "6NUM")
      (footprint "SWITCH_U1_W_LED")
      (libsource (lib "General") (part "MX_SWITCH_SINGLE_W_SMD_LED"))
    )
    (comp (ref "SW76")
      (value "LSHIFT")
      (footprint "SWITCH_U2.25_W_LED")
      (libsource (lib "General") (part "MX_SWITCH_SINGLE_W_SMD_LED"))
    )
    (comp (ref "SW77")
      (value "Z")
      (footprint "SWITCH_U1_W_LED")
      (libsource (lib "General") (part "MX_SWITCH_SINGLE_W_SMD_LED"))
    )
    (comp (ref "SW78")
      (value "X")
      (footprint "SWITCH_U1_W_LED")
      (libsource (lib "General") (part "MX_SWITCH_SINGLE_W_SMD_LED"))
    )
    (comp (ref "SW79")
      (value "C")
      (footprint "SWITCH_U1_W_LED")
      (libsource (lib "General") (part "MX_SWITCH_SINGLE_W_SMD_LED"))
    )
    (comp (ref "SW80")
      (value "V")
      (footprint "SWITCH_U1_W_LED")
      (libsource (lib "General") (part "MX_SWITCH_SINGLE_W_SMD_LED"))
    )
    (comp (ref "SW81")
      (value "B")
      (footprint "SWITCH_U1_W_LED")
      (libsource (lib "General") (part "MX_SWITCH_SINGLE_W_SMD_LED"))
    )
    (comp (ref "SW82")
      (value "N")
      (footprint "SWITCH_U1_W_LED")
      (libsource (lib "General") (part "MX_SWITCH_SINGLE_W_SMD_LED"))
    )
    (comp (ref "SW83")
      (value "M")
      (footprint "SWITCH_U1_W_LED")
      (libsource (lib "General") (part "MX_SWITCH_SINGLE_W_SMD_LED"))
    )
    (comp (ref "SW84")
      (value ",")
      (footprint "SWITCH_U1_W_LED")
      (libsource (lib "General") (part "MX_SWITCH_SINGLE_W_SMD_LED"))
    )
    (comp (ref "SW85")
      (value ".")
      (footprint "SWITCH_U1_W_LED")
      (libsource (lib "General") (part "MX_SWITCH_SINGLE_W_SMD_LED"))
    )
    (comp (ref "SW86")
      (value "/")
      (footprint "SWITCH_U1_W_LED")
      (libsource (lib "General") (part "MX_SWITCH_SINGLE_W_SMD_LED"))
    )
    (comp (ref "SW87")
      (value "RSHIFT")
      (footprint "SWITCH_U2.75_W_LED")
      (libsource (lib "General") (part "MX_SWITCH_SINGLE_W_SMD_LED"))
    )
    (comp (ref "SW88")
      (value "UP")
      (footprint "SWITCH_U1_W_LED")
      (libsource (lib "General") (part "MX_SWITCH_SINGLE_W_SMD_LED"))
    )
    (comp (ref "SW89")
      (value "PAGEDOWN")
      (footprint "SWITCH_U1_W_LED")
      (libsource (lib "General") (part "MX_SWITCH_SINGLE_W_SMD_LED"))
    )
    (comp (ref "SW90")
      (value "1NUM")
      (footprint "SWITCH_U1_W_LED")
      (libsource (lib "General") (part "MX_SWITCH_SINGLE_W_SMD_LED"))
    )
    (comp (ref "SW91")
      (value "2NUM")
      (footprint "SWITCH_U1_W_LED")
      (libsource (lib "General") (part "MX_SWITCH_SINGLE_W_SMD_LED"))
    )
    (comp (ref "SW92")
      (value "3NUM")
      (footprint "SWITCH_U1_W_LED")
      (libsource (lib "General") (part "MX_SWITCH_SINGLE_W_SMD_LED"))
    )
    (comp (ref "SW93")
      (value "ENTERNUM")
      (footprint "SWITCH_U2_W_LED - vert")
      (libsource (lib "General") (part "MX_SWITCH_SINGLE_W_SMD_LED"))
    )
    (comp (ref "SW94")
      (value "LCTRL")
      (footprint "SWITCH_U1.25_W_LED")
      (libsource (lib "General") (part "MX_SWITCH_SINGLE_W_SMD_LED"))
    )
    (comp (ref "SW95")
      (value "LSUPER")
      (footprint "SWITCH_U1.25_W_LED")
      (libsource (lib "General") (part "MX_SWITCH_SINGLE_W_SMD_LED"))
    )
    (comp (ref "SW96")
      (value "lALT")
      (footprint "SWITCH_U1.25_W_LED")
      (libsource (lib "General") (part "MX_SWITCH_SINGLE_W_SMD_LED"))
    )
    (comp (ref "SW97")
      (value "SPACE")
      (footprint "SWITCH_U6.25_W_LED - duplicate")
      (libsource (lib "General") (part "MX_SWITCH_SINGLE_W_SMD_LED"))
    )
    (comp (ref "SW98")
      (value "RCTRL")
      (footprint "SWITCH_U1_W_LED")
      (libsource (lib "General") (part "MX_SWITCH_SINGLE_W_SMD_LED"))
    )
    (comp (ref "SW99")
      (value "RSUPER")
      (footprint "SWITCH_U1_W_LED")
      (libsource (lib "General") (part "MX_SWITCH_SINGLE_W_SMD_LED"))
    )
    (comp (ref "SW100")
      (value "RALT")
      (footprint "SWITCH_U1_W_LED")
      (libsource (lib "General") (part "MX_SWITCH_SINGLE_W_SMD_LED"))
    )
    (comp (ref "SW101")
      (value "FN")
      (footprint "SWITCH_U1_W_LED")
      (libsource (lib "General") (part "MX_SWITCH_SINGLE_W_SMD_LED"))
    )
    (comp (ref "SW102")
      (value "LEFT")
      (footprint "SWITCH_U1_W_LED")
      (libsource (lib "General") (part "MX_SWITCH_SINGLE_W_SMD_LED"))
    )
    (comp (ref "SW103")
      (value "DOWN")
      (footprint "SWITCH_U1_W_LED")
      (libsource (lib "General") (part "MX_SWITCH_SINGLE_W_SMD_LED"))
    )
    (comp (ref "SW104")
      (value "RIGHT")
      (footprint "SWITCH_U1_W_LED")
      (libsource (lib "General") (part "MX_SWITCH_SINGLE_W_SMD_LED"))
    )
    (comp (ref "SW105")
      (value "0NUM")
      (footprint "SWITCH_U2_W_LED")
      (libsource (lib "General") (part "MX_SWITCH_SINGLE_W_SMD_LED"))
    )
    (comp (ref "SW106")
      (value ".NUM")
      (footprint "SWITCH_U1_W_LED")
      (libsource (lib "General") (part "MX_SWITCH_SINGLE_W_SMD_LED"))
    )
  )
  (nets
    (net (code "1") (name "/SWC1") (class "Default")
      (node (ref "D1") (pin "1") (pinfunction "1_1") (pintype "passive"))
      (node (ref "D18") (pin "1") (pinfunction "1_1") (pintype "passive"))
      (node (ref "D38") (pin "1") (pinfunction "1_1") (pintype "passive"))
      (node (ref "D58") (pin "1") (pinfunction "1_1") (pintype "passive"))
      (node (ref "D76") (pin "1") (pinfunction "1_1") (pintype "passive"))
      (node (ref "D94") (pin "1") (pinfunction "1_1") (pintype "passive"))
    )
    (net (code "2") (name "/SWC2") (class "Default")
      (node (ref "D19") (pin "1") (pinfunction "1_1") (pintype "passive"))
      (node (ref "D2") (pin "1") (pinfunction "1_1") (pintype "passive"))
      (node (ref "D39") (pin "1") (pinfunction "1_1") (pintype "passive"))
      (node (ref "D59") (pin "1") (pinfunction "1_1") (pintype "passive"))
      (node (ref "D77") (pin "1") (pinfunction "1_1") (pintype "passive"))
      (node (ref "D95") (pin "1") (pinfunction "1_1") (pintype "passive"))
    )
    (net (code "3") (name "/SWC3") (class "Default")
      (node (ref "D20") (pin "1") (pinfunction "1_1") (pintype "passive"))
      (node (ref "D3") (pin "1") (pinfunction "1_1") (pintype "passive"))
      (node (ref "D40") (pin "1") (pinfunction "1_1") (pintype "passive"))
      (node (ref "D60") (pin "1") (pinfunction "1_1") (pintype "passive"))
      (node (ref "D78") (pin "1") (pinfunction "1_1") (pintype "passive"))
      (node (ref "D96") (pin "1") (pinfunction "1_1") (pintype "passive"))
    )
    (net (code "4") (name "/SWC4") (class "Default")
      (node (ref "D21") (pin "1") (pinfunction "1_1") (pintype "passive"))
      (node (ref "D4") (pin "1") (pinfunction "1_1") (pintype "passive"))
      (node (ref "D41") (pin "1") (pinfunction "1_1") (pintype "passive"))
      (node (ref "D61") (pin "1") (pinfunction "1_1") (pintype "passive"))
      (node (ref "D79") (pin "1") (pinfunction "1_1") (pintype "passive"))
    )
    (net (code "5") (name "/SWC5") (class "Default")
      (node (ref "D22") (pin "1") (pinfunction "1_1") (pintype "passive"))
      (node (ref "D42") (pin "1") (pinfunction "1_1") (pintype "passive"))
      (node (ref "D5") (pin "1") (pinfunction "1_1") (pintype "passive"))
      (node (ref "D62") (pin "1") (pinfunction "1_1") (pintype "passive"))
      (node (ref "D80") (pin "1") (pinfunction "1_1") (pintype "passive"))
    )
    (net (code "6") (name "/SWC6") (class "Default")
      (node (ref "D23") (pin "1") (pinfunction "1_1") (pintype "passive"))
      (node (ref "D43") (pin "1") (pinfunction "1_1") (pintype "passive"))
      (node (ref "D6") (pin "1") (pinfunction "1_1") (pintype "passive"))
      (node (ref "D63") (pin "1") (pinfunction "1_1") (pintype "passive"))
      (node (ref "D81") (pin "1") (pinfunction "1_1") (pintype "passive"))
      (node (ref "D97") (pin "1") (pinfunction "1_1") (pintype "passive"))
    )
    (net (code "7") (name "/SWC7") (class "Default")
      (node (ref "D24") (pin "1") (pinfunction "1_1") (pintype "passive"))
      (node (ref "D44") (pin "1") (pinfunction "1_1") (pintype "passive"))
      (node (ref "D64") (pin "1") (pinfunction "1_1") (pintype "passive"))
      (node (ref "D7") (pin "1") (pinfunction "1_1") (pintype "passive"))
      (node (ref "D82") (pin "1") (pinfunction "1_1") (pintype "passive"))
    )
    (net (code "8") (name "/SWC8") (class "Default")
      (node (ref "D25") (pin "1") (pinfunction "1_1") (pintype "passive"))
      (node (ref "D45") (pin "1") (pinfunction "1_1") (pintype "passive"))
      (node (ref "D65") (pin "1") (pinfunction "1_1") (pintype "passive"))
      (node (ref "D8") (pin "1") (pinfunction "1_1") (pintype "passive"))
      (node (ref "D83") (pin "1") (pinfunction "1_1") (pintype "passive"))
    )
    (net (code "9") (name "/SWC9") (class "Default")
      (node (ref "D26") (pin "1") (pinfunction "1_1") (pintype "passive"))
      (node (ref "D46") (pin "1") (pinfunction "1_1") (pintype "passive"))
      (node (ref "D66") (pin "1") (pinfunction "1_1") (pintype "passive"))
      (node (ref "D84") (pin "1") (pinfunction "1_1") (pintype "passive"))
      (node (ref "D9") (pin "1") (pinfunction "1_1") (pintype "passive"))
      (node (ref "D98") (pin "1") (pinfunction "1_1") (pintype "passive"))
    )
    (net (code "10") (name "/SWC10") (class "Default")
      (node (ref "D10") (pin "1") (pinfunction "1_1") (pintype "passive"))
      (node (ref "D27") (pin "1") (pinfunction "1_1") (pintype "passive"))
      (node (ref "D47") (pin "1") (pinfunction "1_1") (pintype "passive"))
      (node (ref "D67") (pin "1") (pinfunction "1_1") (pintype "passive"))
      (node (ref "D85") (pin "1") (pinfunction "1_1") (pintype "passive"))
      (node (ref "D99") (pin "1") (pinfunction "1_1") (pintype "passive"))
    )
    (net (code "11") (name "/SWC11") (class "Default")
      (node (ref "D100") (pin "1") (pinfunction "1_1") (pintype "passive"))
      (node (ref "D11") (pin "1") (pinfunction "1_1") (pintype "passive"))
      (node (ref "D28") (pin "1") (pinfunction "1_1") (pintype "passive"))
      (node (ref "D48") (pin "1") (pinfunction "1_1") (pintype "passive"))
      (node (ref "D68") (pin "1") (pinfunction "1_1") (pintype "passive"))
      (node (ref "D86") (pin "1") (pinfunction "1_1") (pintype "passive"))
    )
    (net (code "12") (name "/SWC12") (class "Default")
      (node (ref "D101") (pin "1") (pinfunction "1_1") (pintype "passive"))
      (node (ref "D12") (pin "1") (pinfunction "1_1") (pintype "passive"))
      (node (ref "D29") (pin "1") (pinfunction "1_1") (pintype "passive"))
      (node (ref "D49") (pin "1") (pinfunction "1_1") (pintype "passive"))
      (node (ref "D69") (pin "1") (pinfunction "1_1") (pintype "passive"))
    )
    (net (code "13") (name "/SWC13") (class "Default")
      (node (ref "D13") (pin "1") (pinfunction "1_1") (pintype "passive"))
      (node (ref "D30") (pin "1") (pinfunction "1_1") (pintype "passive"))
      (node (ref "D50") (pin "1") (pinfunction "1_1") (pintype "passive"))
    )
    (net (code "14") (name "/SWC14") (class "Default")
      (node (ref "D102") (pin "1") (pinfunction "1_1") (pintype "passive"))
      (node (ref "D14") (pin "1") (pinfunction "1_1") (pintype "passive"))
      (node (ref "D31") (pin "1") (pinfunction "1_1") (pintype "passive"))
      (node (ref "D51") (pin "1") (pinfunction "1_1") (pintype "passive"))
      (node (ref "D70") (pin "1") (pinfunction "1_1") (pintype "passive"))
      (node (ref "D87") (pin "1") (pinfunction "1_1") (pintype "passive"))
    )
    (net (code "15") (name "/SWC15") (class "Default")
      (node (ref "D103") (pin "1") (pinfunction "1_1") (pintype "passive"))
      (node (ref "D15") (pin "1") (pinfunction "1_1") (pintype "passive"))
      (node (ref "D32") (pin "1") (pinfunction "1_1") (pintype "passive"))
      (node (ref "D52") (pin "1") (pinfunction "1_1") (pintype "passive"))
      (node (ref "D71") (pin "1") (pinfunction "1_1") (pintype "passive"))
      (node (ref "D88") (pin "1") (pinfunction "1_1") (pintype "passive"))
    )
    (net (code "16") (name "/SWC16") (class "Default")
      (node (ref "D104") (pin "1") (pinfunction "1_1") (pintype "passive"))
      (node (ref "D16") (pin "1") (pinfunction "1_1") (pintype "passive"))
      (node (ref "D33") (pin "1") (pinfunction "1_1") (pintype "passive"))
      (node (ref "D53") (pin "1") (pinfunction "1_1") (pintype "passive"))
      (node (ref "D72") (pin "1") (pinfunction "1_1") (pintype "passive"))
      (node (ref "D89") (pin "1") (pinfunction "1_1") (pintype "passive"))
    )
    (net (code "17") (name "/SWC17") (class "Default")
      (node (ref "D105") (pin "1") (pinfunction "1_1") (pintype "passive"))
      (node (ref "D17") (pin "1") (pinfunction "1_1") (pintype "passive"))
      (node (ref "D34") (pin "1") (pinfunction "1_1") (pintype "passive"))
      (node (ref "D54") (pin "1") (pinfunction "1_1") (pintype "passive"))
      (node (ref "D73") (pin "1") (pinfunction "1_1") (pintype "passive"))
      (node (ref "D90") (pin "1") (pinfunction "1_1") (pintype "passive"))
    )
    (net (code "18") (name "/SWC18") (class "Default")
      (node (ref "D35") (pin "1") (pinfunction "1_1") (pintype "passive"))
      (node (ref "D55") (pin "1") (pinfunction "1_1") (pintype "passive"))
      (node (ref "D74") (pin "1") (pinfunction "1_1") (pintype "passive"))
      (node (ref "D91") (pin "1") (pinfunction "1_1") (pintype "passive"))
    )
    (net (code "19") (name "/SWC19") (class "Default")
      (node (ref "D106") (pin "1") (pinfunction "1_1") (pintype "passive"))
      (node (ref "D36") (pin "1") (pinfunction "1_1") (pintype "passive"))
      (node (ref "D56") (pin "1") (pinfunction "1_1") (pintype "passive"))
      (node (ref "D75") (pin "1") (pinfunction "1_1") (pintype "passive"))
      (node (ref "D92") (pin "1") (pinfunction "1_1") (pintype "passive"))
    )
    (net (code "20") (name "/SWC20") (class "Default")
      (node (ref "D37") (pin "1") (pinfunction "1_1") (pintype "passive"))
      (node (ref "D57") (pin "1") (pinfunction "1_1") (pintype "passive"))
      (node (ref "D93") (pin "1") (pinfunction "1_1") (pintype "passive"))
    )
    (net (code "21") (name "/SWROW1") (class "Default")
      (node (ref "SW1") (pin "1") (pintype "passive"))
      (node (ref "SW10") (pin "1") (pintype "passive"))
      (node (ref "SW11") (pin "1") (pintype "passive"))
      (node (ref "SW12") (pin "1") (pintype "passive"))
      (node (ref "SW13") (pin "1") (pintype "passive"))
      (node (ref "SW14") (pin "1") (pintype "passive"))
      (node (ref "SW15") (pin "1") (pintype "passive"))
      (node (ref "SW16") (pin "1") (pintype "passive"))
      (node (ref "SW17") (pin "1") (pintype "passive"))
      (node (ref "SW2") (pin "1") (pintype "passive"))
      (node (ref "SW3") (pin "1") (pintype "passive"))
      (node (ref "SW4") (pin "1") (pintype "passive"))
      (node (ref "SW5") (pin "1") (pintype "passive"))
      (node (ref "SW6") (pin "1") (pintype "passive"))
      (node (ref "SW7") (pin "1") (pintype "passive"))
      (node (ref "SW8") (pin "1") (pintype "passive"))
      (node (ref "SW9") (pin "1") (pintype "passive"))
    )
    (net (code "22") (name "/SWROW2") (class "Default")
      (node (ref "SW18") (pin "1") (pintype "passive"))
      (node (ref "SW19") (pin "1") (pintype "passive"))
      (node (ref "SW20") (pin "1") (pintype "passive"))
      (node (ref "SW21") (pin "1") (pintype "passive"))
      (node (ref "SW22") (pin "1") (pintype "passive"))
      (node (ref "SW23") (pin "1") (pintype "passive"))
      (node (ref "SW24") (pin "1") (pintype "passive"))
      (node (ref "SW25") (pin "1") (pintype "passive"))
      (node (ref "SW26") (pin "1") (pintype "passive"))
      (node (ref "SW27") (pin "1") (pintype "passive"))
      (node (ref "SW28") (pin "1") (pintype "passive"))
      (node (ref "SW29") (pin "1") (pintype "passive"))
      (node (ref "SW30") (pin "1") (pintype "passive"))
      (node (ref "SW31") (pin "1") (pintype "passive"))
      (node (ref "SW32") (pin "1") (pintype "passive"))
      (node (ref "SW33") (pin "1") (pintype "passive"))
      (node (ref "SW34") (pin "1") (pintype "passive"))
      (node (ref "SW35") (pin "1") (pintype "passive"))
      (node (ref "SW36") (pin "1") (pintype "passive"))
      (node (ref "SW37") (pin "1") (pintype "passive"))
    )
    (net (code "23") (name "/SWROW3") (class "Default")
      (node (ref "SW38") (pin "1") (pintype "passive"))
      (node (ref "SW39") (pin "1") (pintype "passive"))
      (node (ref "SW40") (pin "1") (pintype "passive"))
      (node (ref "SW41") (pin "1") (pintype "passive"))
      (node (ref "SW42") (pin "1") (pintype "passive"))
      (node (ref "SW43") (pin "1") (pintype "passive"))
      (node (ref "SW44") (pin "1") (pintype "passive"))
      (node (ref "SW45") (pin "1") (pintype "passive"))
      (node (ref "SW46") (pin "1") (pintype "passive"))
      (node (ref "SW47") (pin "1") (pintype "passive"))
      (node (ref "SW48") (pin "1") (pintype "passive"))
      (node (ref "SW49") (pin "1") (pintype "passive"))
      (node (ref "SW50") (pin "1") (pintype "passive"))
      (node (ref "SW51") (pin "1") (pintype "passive"))
      (node (ref "SW52") (pin "1") (pintype "passive"))
      (node (ref "SW53") (pin "1") (pintype "passive"))
      (node (ref "SW54") (pin "1") (pintype "passive"))
      (node (ref "SW55") (pin "1") (pintype "passive"))
      (node (ref "SW56") (pin "1") (pintype "passive"))
      (node (ref "SW57") (pin "1") (pintype "passive"))
    )
    (net (code "24") (name "/SWROW4") (class "Default")
      (node (ref "SW58") (pin "1") (pintype "passive"))
      (node (ref "SW59") (pin "1") (pintype "passive"))
      (node (ref "SW60") (pin "1") (pintype "passive"))
      (node (ref "SW61") (pin "1") (pintype "passive"))
      (node (ref "SW62") (pin "1") (pintype "passive"))
      (node (ref "SW63") (pin "1") (pintype "passive"))
      (node (ref "SW64") (pin "1") (pintype "passive"))
      (node (ref "SW65") (pin "1") (pintype "passive"))
      (node (ref "SW66") (pin "1") (pintype "passive"))
      (node (ref "SW67") (pin "1") (pintype "passive"))
      (node (ref "SW68") (pin "1") (pintype "passive"))
      (node (ref "SW69") (pin "1") (pintype "passive"))
      (node (ref "SW70") (pin "1") (pintype "passive"))
      (node (ref "SW71") (pin "1") (pintype "passive"))
      (node (ref "SW72") (pin "1") (pintype "passive"))
      (node (ref "SW73") (pin "1") (pintype "passive"))
      (node (ref "SW74") (pin "1") (pintype "passive"))
      (node (ref "SW75") (pin "1") (pintype "passive"))
    )
    (net (code "25") (name "/SWROW5") (class "Default")
      (node (ref "SW76") (pin "1") (pintype "passive"))
      (node (ref "SW77") (pin "1") (pintype "passive"))
      (node (ref "SW78") (pin "1") (pintype "passive"))
      (node (ref "SW79") (pin "1") (pintype "passive"))
      (node (ref "SW80") (pin "1") (pintype "passive"))
      (node (ref "SW81") (pin "1") (pintype "passive"))
      (node (ref "SW82") (pin "1") (pintype "passive"))
      (node (ref "SW83") (pin "1") (pintype "passive"))
      (node (ref "SW84") (pin "1") (pintype "passive"))
      (node (ref "SW85") (pin "1") (pintype "passive"))
      (node (ref "SW86") (pin "1") (pintype "passive"))
      (node (ref "SW87") (pin "1") (pintype "passive"))
      (node (ref "SW88") (pin "1") (pintype "passive"))
      (node (ref "SW89") (pin "1") (pintype "passive"))
      (node (ref "SW90") (pin "1") (pintype "passive"))
      (node (ref "SW91") (pin "1") (pintype "passive"))
      (node (ref "SW92") (pin "1") (pintype "passive"))
      (node (ref "SW93") (pin "1") (pintype "passive"))
    )
    (net (code "26") (name "/SWROW6") (class "Default")
      (node (ref "SW100") (pin "1") (pintype "passive"))
      (node (ref "SW101") (pin "1") (pintype "passive"))
      (node (ref "SW102") (pin "1") (pintype "passive"))
      (node (ref "SW103") (pin "1") (pintype "passive"))
      (node (ref "SW104") (pin "1") (pintype "passive"))
      (node (ref "SW105") (pin "1") (pintype "passive"))
      (node (ref "SW106") (pin "1") (pintype "passive"))
      (node (ref "SW94") (pin "1") (pintype "passive"))
      (node (ref "SW95") (pin "1") (pintype "passive"))
      (node (ref "SW96") (pin "1") (pintype "passive"))
      (node (ref "SW97") (pin "1") (pintype "passive"))
      (node (ref "SW98") (pin "1") (pintype "passive"))
      (node (ref "SW99") (pin "1") (pintype "passive"))
    )
    (net (code "27") (name "Net-(D1-Pad2)") (class "Default")
      (node (ref "D1") (pin "2") (pinfunction "2_2") (pintype "passive"))
      (node (ref "SW1") (pin "2") (pintype "passive"))
    )
    (net (code "28") (name "Net-(D2-Pad2)") (class "Default")
      (node (ref "D2") (pin "2") (pinfunction "2_2") (pintype "passive"))
      (node (ref "SW2") (pin "2") (pintype "passive"))
    )
    (net (code "29") (name "Net-(D3-Pad2)") (class "Default")
      (node (ref "D3") (pin "2") (pinfunction "2_2") (pintype "passive"))
      (node (ref "SW3") (pin "2") (pintype "passive"))
    )
    (net (code "30") (name "Net-(D4-Pad2)") (class "Default")
      (node (ref "D4") (pin "2") (pinfunction "2_2") (pintype "passive"))
      (node (ref "SW4") (pin "2") (pintype "passive"))
    )
    (net (code "31") (name "Net-(D5-Pad2)") (class "Default")
      (node (ref "D5") (pin "2") (pinfunction "2_2") (pintype "passive"))
      (node (ref "SW5") (pin "2") (pintype "passive"))
    )
    (net (code "32") (name "Net-(D6-Pad2)") (class "Default")
      (node (ref "D6") (pin "2") (pinfunction "2_2") (pintype "passive"))
      (node (ref "SW6") (pin "2") (pintype "passive"))
    )
    (net (code "33") (name "Net-(D7-Pad2)") (class "Default")
      (node (ref "D7") (pin "2") (pinfunction "2_2") (pintype "passive"))
      (node (ref "SW7") (pin "2") (pintype "passive"))
    )
    (net (code "34") (name "Net-(D8-Pad2)") (class "Default")
      (node (ref "D8") (pin "2") (pinfunction "2_2") (pintype "passive"))
      (node (ref "SW8") (pin "2") (pintype "passive"))
    )
    (net (code "35") (name "Net-(D9-Pad2)") (class "Default")
      (node (ref "D9") (pin "2") (pinfunction "2_2") (pintype "passive"))
      (node (ref "SW9") (pin "2") (pintype "passive"))
    )
    (net (code "36") (name "Net-(D10-Pad2)") (class "Default")
      (node (ref "D10") (pin "2") (pinfunction "2_2") (pintype "passive"))
      (node (ref "SW10") (pin "2") (pintype "passive"))
    )
    (net (code "37") (name "Net-(D11-Pad2)") (class "Default")
      (node (ref "D11") (pin "2") (pinfunction "2_2") (pintype "passive"))
      (node (ref "SW11") (pin "2") (pintype "passive"))
    )
    (net (code "38") (name "Net-(D12-Pad2)") (class "Default")
      (node (ref "D12") (pin "2") (pinfunction "2_2") (pintype "passive"))
      (node (ref "SW12") (pin "2") (pintype "passive"))
    )
    (net (code "39") (name "Net-(D13-Pad2)") (class "Default")
      (node (ref "D13") (pin "2") (pinfunction "2_2") (pintype "passive"))
      (node (ref "SW13") (pin "2") (pintype "passive"))
    )
    (net (code "40") (name "Net-(D14-Pad2)") (class "Default")
      (node (ref "D14") (pin "2") (pinfunction "2_2") (pintype "passive"))
      (node (ref "SW14") (pin "2") (pintype "passive"))
    )
    (net (code "41") (name "Net-(D15-Pad2)") (class "Default")
      (node (ref "D15") (pin "2") (pinfunction "2_2") (pintype "passive"))
      (node (ref "SW15") (pin "2") (pintype "passive"))
    )
    (net (code "42") (name "Net-(D16-Pad2)") (class "Default")
      (node (ref "D16") (pin "2") (pinfunction "2_2") (pintype "passive"))
      (node (ref "SW16") (pin "2") (pintype "passive"))
    )
    (net (code "43") (name "Net-(D17-Pad2)") (class "Default")
      (node (ref "D17") (pin "2") (pinfunction "2_2") (pintype "passive"))
      (node (ref "SW17") (pin "2") (pintype "passive"))
    )
    (net (code "44") (name "Net-(D18-Pad2)") (class "Default")
      (node (ref "D18") (pin "2") (pinfunction "2_2") (pintype "passive"))
      (node (ref "SW18") (pin "2") (pintype "passive"))
    )
    (net (code "45") (name "Net-(D19-Pad2)") (class "Default")
      (node (ref "D19") (pin "2") (pinfunction "2_2") (pintype "passive"))
      (node (ref "SW19") (pin "2") (pintype "passive"))
    )
    (net (code "46") (name "Net-(D20-Pad2)") (class "Default")
      (node (ref "D20") (pin "2") (pinfunction "2_2") (pintype "passive"))
      (node (ref "SW20") (pin "2") (pintype "passive"))
    )
    (net (code "47") (name "Net-(D21-Pad2)") (class "Default")
      (node (ref "D21") (pin "2") (pinfunction "2_2") (pintype "passive"))
      (node (ref "SW21") (pin "2") (pintype "passive"))
    )
    (net (code "48") (name "Net-(D22-Pad2)") (class "Default")
      (node (ref "D22") (pin "2") (pinfunction "2_2") (pintype "passive"))
      (node (ref "SW22") (pin "2") (pintype "passive"))
    )
    (net (code "49") (name "Net-(D23-Pad2)") (class "Default")
      (node (ref "D23") (pin "2") (pinfunction "2_2") (pintype "passive"))
      (node (ref "SW23") (pin "2") (pintype "passive"))
    )
    (net (code "50") (name "Net-(D24-Pad2)") (class "Default")
      (node (ref "D24") (pin "2") (pinfunction "2_2") (pintype "passive"))
      (node (ref "SW24") (pin "2") (pintype "passive"))
    )
    (net (code "51") (name "Net-(D25-Pad2)") (class "Default")
      (node (ref "D25") (pin "2") (pinfunction "2_2") (pintype "passive"))
      (node (ref "SW25") (pin "2") (pintype "passive"))
    )
    (net (code "52") (name "Net-(D26-Pad2)") (class "Default")
      (node (ref "D26") (pin "2") (pinfunction "2_2") (pintype "passive"))
      (node (ref "SW26") (pin "2") (pintype "passive"))
    )
    (net (code "53") (name "Net-(D27-Pad2)") (class "Default")
      (node (ref "D27") (pin "2") (pinfunction "2_2") (pintype "passive"))
      (node (ref "SW27") (pin "2") (pintype "passive"))
    )
    (net (code "54") (name "Net-(D28-Pad2)") (class "Default")
      (node (ref "D28") (pin "2") (pinfunction "2_2") (pintype "passive"))
      (node (ref "SW28") (pin "2") (pintype "passive"))
    )
    (net (code "55") (name "Net-(D29-Pad2)") (class "Default")
      (node (ref "D29") (pin "2") (pinfunction "2_2") (pintype "passive"))
      (node (ref "SW29") (pin "2") (pintype "passive"))
    )
    (net (code "56") (name "Net-(D30-Pad2)") (class "Default")
      (node (ref "D30") (pin "2") (pinfunction "2_2") (pintype "passive"))
      (node (ref "SW30") (pin "2") (pintype "passive"))
    )
    (net (code "57") (name "Net-(D31-Pad2)") (class "Default")
      (node (ref "D31") (pin "2") (pinfunction "2_2") (pintype "passive"))
      (node (ref "SW31") (pin "2") (pintype "passive"))
    )
    (net (code "58") (name "Net-(D32-Pad2)") (class "Default")
      (node (ref "D32") (pin "2") (pinfunction "2_2") (pintype "passive"))
      (node (ref "SW32") (pin "2") (pintype "passive"))
    )
    (net (code "59") (name "Net-(D33-Pad2)") (class "Default")
      (node (ref "D33") (pin "2") (pinfunction "2_2") (pintype "passive"))
      (node (ref "SW33") (pin "2") (pintype "passive"))
    )
    (net (code "60") (name "Net-(D34-Pad2)") (class "Default")
      (node (ref "D34") (pin "2") (pinfunction "2_2") (pintype "passive"))
      (node (ref "SW34") (pin "2") (pintype "passive"))
    )
    (net (code "61") (name "Net-(D35-Pad2)") (class "Default")
      (node (ref "D35") (pin "2") (pinfunction "2_2") (pintype "passive"))
      (node (ref "SW35") (pin "2") (pintype "passive"))
    )
    (net (code "62") (name "Net-(D36-Pad2)") (class "Default")
      (node (ref "D36") (pin "2") (pinfunction "2_2") (pintype "passive"))
      (node (ref "SW36") (pin "2") (pintype "passive"))
    )
    (net (code "63") (name "Net-(D37-Pad2)") (class "Default")
      (node (ref "D37") (pin "2") (pinfunction "2_2") (pintype "passive"))
      (node (ref "SW37") (pin "2") (pintype "passive"))
    )
    (net (code "64") (name "Net-(D38-Pad2)") (class "Default")
      (node (ref "D38") (pin "2") (pinfunction "2_2") (pintype "passive"))
      (node (ref "SW38") (pin "2") (pintype "passive"))
    )
    (net (code "65") (name "Net-(D39-Pad2)") (class "Default")
      (node (ref "D39") (pin "2") (pinfunction "2_2") (pintype "passive"))
      (node (ref "SW39") (pin "2") (pintype "passive"))
    )
    (net (code "66") (name "Net-(D40-Pad2)") (class "Default")
      (node (ref "D40") (pin "2") (pinfunction "2_2") (pintype "passive"))
      (node (ref "SW40") (pin "2") (pintype "passive"))
    )
    (net (code "67") (name "Net-(D41-Pad2)") (class "Default")
      (node (ref "D41") (pin "2") (pinfunction "2_2") (pintype "passive"))
      (node (ref "SW41") (pin "2") (pintype "passive"))
    )
    (net (code "68") (name "Net-(D42-Pad2)") (class "Default")
      (node (ref "D42") (pin "2") (pinfunction "2_2") (pintype "passive"))
      (node (ref "SW42") (pin "2") (pintype "passive"))
    )
    (net (code "69") (name "Net-(D43-Pad2)") (class "Default")
      (node (ref "D43") (pin "2") (pinfunction "2_2") (pintype "passive"))
      (node (ref "SW43") (pin "2") (pintype "passive"))
    )
    (net (code "70") (name "Net-(D44-Pad2)") (class "Default")
      (node (ref "D44") (pin "2") (pinfunction "2_2") (pintype "passive"))
      (node (ref "SW44") (pin "2") (pintype "passive"))
    )
    (net (code "71") (name "Net-(D45-Pad2)") (class "Default")
      (node (ref "D45") (pin "2") (pinfunction "2_2") (pintype "passive"))
      (node (ref "SW45") (pin "2") (pintype "passive"))
    )
    (net (code "72") (name "Net-(D46-Pad2)") (class "Default")
      (node (ref "D46") (pin "2") (pinfunction "2_2") (pintype "passive"))
      (node (ref "SW46") (pin "2") (pintype "passive"))
    )
    (net (code "73") (name "Net-(D47-Pad2)") (class "Default")
      (node (ref "D47") (pin "2") (pinfunction "2_2") (pintype "passive"))
      (node (ref "SW47") (pin "2") (pintype "passive"))
    )
    (net (code "74") (name "Net-(D48-Pad2)") (class "Default")
      (node (ref "D48") (pin "2") (pinfunction "2_2") (pintype "passive"))
      (node (ref "SW48") (pin "2") (pintype "passive"))
    )
    (net (code "75") (name "Net-(D49-Pad2)") (class "Default")
      (node (ref "D49") (pin "2") (pinfunction "2_2") (pintype "passive"))
      (node (ref "SW49") (pin "2") (pintype "passive"))
    )
    (net (code "76") (name "Net-(D50-Pad2)") (class "Default")
      (node (ref "D50") (pin "2") (pinfunction "2_2") (pintype "passive"))
      (node (ref "SW50") (pin "2") (pintype "passive"))
    )
    (net (code "77") (name "Net-(D51-Pad2)") (class "Default")
      (node (ref "D51") (pin "2") (pinfunction "2_2") (pintype "passive"))
      (node (ref "SW51") (pin "2") (pintype "passive"))
    )
    (net (code "78") (name "Net-(D52-Pad2)") (class "Default")
      (node (ref "D52") (pin "2") (pinfunction "2_2") (pintype "passive"))
      (node (ref "SW52") (pin "2") (pintype "passive"))
    )
    (net (code "79") (name "Net-(D53-Pad2)") (class "Default")
      (node (ref "D53") (pin "2") (pinfunction "2_2") (pintype "passive"))
      (node (ref "SW53") (pin "2") (pintype "passive"))
    )
    (net (code "80") (name "Net-(D54-Pad2)") (class "Default")
      (node (ref "D54") (pin "2") (pinfunction "2_2") (pintype "passive"))
      (node (ref "SW54") (pin "2") (pintype "passive"))
    )
    (net (code "81") (name "Net-(D55-Pad2)") (class "Default")
      (node (ref "D55") (pin "2") (pinfunction "2_2") (pintype "passive"))
      (node (ref "SW55") (pin "2") (pintype "passive"))
    )
    (net (code "82") (name "Net-(D56-Pad2)") (class "Default")
      (node (ref "D56") (pin "2") (pinfunction "2_2") (pintype "passive"))
      (node (ref "SW56") (pin "2") (pintype "passive"))
    )
    (net (code "83") (name "Net-(D57-Pad2)") (class "Default")
      (node (ref "D57") (pin "2") (pinfunction "2_2") (pintype "passive"))
      (node (ref "SW57") (pin "2") (pintype "passive"))
    )
    (net (code "84") (name "Net-(D58-Pad2)") (class "Default")
      (node (ref "D58") (pin "2") (pinfunction "2_2") (pintype "passive"))
      (node (ref "SW58") (pin "2") (pintype "passive"))
    )
    (net (code "85") (name "Net-(D59-Pad2)") (class "Default")
      (node (ref "D59") (pin "2") (pinfunction "2_2") (pintype "passive"))
      (node (ref "SW59") (pin "2") (pintype "passive"))
    )
    (net (code "86") (name "Net-(D60-Pad2)") (class "Default")
      (node (ref "D60") (pin "2") (pinfunction "2_2") (pintype "passive"))
      (node (ref "SW60") (pin "2") (pintype "passive"))
    )
    (net (code "87") (name "Net-(D61-Pad2)") (class "Default")
      (node (ref "D61") (pin "2") (pinfunction "2_2") (pintype "passive"))
      (node (ref "SW61") (pin "2") (pintype "passive"))
    )
    (net (code "88") (name "Net-(D62-Pad2)") (class "Default")
      (node (ref "D62") (pin "2") (pinfunction "2_2") (pintype "passive"))
      (node (ref "SW62") (pin "2") (pintype "passive"))
    )
    (net (code "89") (name "Net-(D63-Pad2)") (class "Default")
      (node (ref "D63") (pin "2") (pinfunction "2_2") (pintype "passive"))
      (node (ref "SW63") (pin "2") (pintype "passive"))
    )
    (net (code "90") (name "Net-(D64-Pad2)") (class "Default")
      (node (ref "D64") (pin "2") (pinfunction "2_2") (pintype "passive"))
      (node (ref "SW64") (pin "2") (pintype "passive"))
    )
    (net (code "91") (name "Net-(D65-Pad2)") (class "Default")
      (node (ref "D65") (pin "2") (pinfunction "2_2") (pintype "passive"))
      (node (ref "SW65") (pin "2") (pintype "passive"))
    )
    (net (code "92") (name "Net-(D66-Pad2)") (class "Default")
      (node (ref "D66") (pin "2") (pinfunction "2_2") (pintype "passive"))
      (node (ref "SW66") (pin "2") (pintype "passive"))
    )
    (net (code "93") (name "Net-(D67-Pad2)") (class "Default")
      (node (ref "D67") (pin "2") (pinfunction "2_2") (pintype "passive"))
      (node (ref "SW67") (pin "2") (pintype "passive"))
    )
    (net (code "94") (name "Net-(D68-Pad2)") (class "Default")
      (node (ref "D68") (pin "2") (pinfunction "2_2") (pintype "passive"))
      (node (ref "SW68") (pin "2") (pintype "passive"))
    )
    (net (code "95") (name "Net-(D69-Pad2)") (class "Default")
      (node (ref "D69") (pin "2") (pinfunction "2_2") (pintype "passive"))
      (node (ref "SW69") (pin "2") (pintype "passive"))
    )
    (net (code "96") (name "Net-(D70-Pad2)") (class "Default")
      (node (ref "D70") (pin "2") (pinfunction "2_2") (pintype "passive"))
      (node (ref "SW70") (pin "2") (pintype "passive"))
    )
    (net (code "97") (name "Net-(D71-Pad2)") (class "Default")
      (node (ref "D71") (pin "2") (pinfunction "2_2") (pintype "passive"))
      (node (ref "SW71") (pin "2") (pintype "passive"))
    )
    (net (code "98") (name "Net-(D72-Pad2)") (class "Default")
      (node (ref "D72") (pin "2") (pinfunction "2_2") (pintype "passive"))
      (node (ref "SW72") (pin "2") (pintype "passive"))
    )
    (net (code "99") (name "Net-(D73-Pad2)") (class "Default")
      (node (ref "D73") (pin "2") (pinfunction "2_2") (pintype "passive"))
      (node (ref "SW73") (pin "2") (pintype "passive"))
    )
    (net (code "100") (name "Net-(D74-Pad2)") (class "Default")
      (node (ref "D74") (pin "2") (pinfunction "2_2") (pintype "passive"))
      (node (ref "SW74") (pin "2") (pintype "passive"))
    )
    (net (code "101") (name "Net-(D75-Pad2)") (class "Default")
      (node (ref "D75") (pin "2") (pinfunction "2_2") (pintype "passive"))
      (node (ref "SW75") (pin "2") (pintype "passive"))
    )
    (net (code "102") (name "Net-(D76-Pad2)") (class "Default")
      (node (ref "D76") (pin "2") (pinfunction "2_2") (pintype "passive"))
      (node (ref "SW76") (pin "2") (pintype "passive"))
    )
    (net (code "103") (name "Net-(D77-Pad2)") (class "Default")
      (node (ref "D77") (pin "2") (pinfunction "2_2") (pintype "passive"))
      (node (ref "SW77") (pin "2") (pintype "passive"))
    )
    (net (code "104") (name "Net-(D78-Pad2)") (class "Default")
      (node (ref "D78") (pin "2") (pinfunction "2_2") (pintype "passive"))
      (node (ref "SW78") (pin "2") (pintype "passive"))
    )
    (net (code "105") (name "Net-(D79-Pad2)") (class "Default")
      (node (ref "D79") (pin "2") (pinfunction "2_2") (pintype "passive"))
      (node (ref "SW79") (pin "2") (pintype "passive"))
    )
    (net (code "106") (name "Net-(D80-Pad2)") (class "Default")
      (node (ref "D80") (pin "2") (pinfunction "2_2") (pintype "passive"))
      (node (ref "SW80") (pin "2") (pintype "passive"))
    )
    (net (code "107") (name "Net-(D81-Pad2)") (class "Default")
      (node (ref "D81") (pin "2") (pinfunction "2_2") (pintype "passive"))
      (node (ref "SW81") (pin "2") (pintype "passive"))
    )
    (net (code "108") (name "Net-(D82-Pad2)") (class "Default")
      (node (ref "D82") (pin "2") (pinfunction "2_2") (pintype "passive"))
      (node (ref "SW82") (pin "2") (pintype "passive"))
    )
    (net (code "109") (name "Net-(D83-Pad2)") (class "Default")
      (node (ref "D83") (pin "2") (pinfunction "2_2") (pintype "passive"))
      (node (ref "SW83") (pin "2") (pintype "passive"))
    )
    (net (code "110") (name "Net-(D84-Pad2)") (class "Default")
      (node (ref "D84") (pin "2") (pinfunction "2_2") (pintype "passive"))
      (node (ref "SW84") (pin "2") (pintype "passive"))
    )
    (net (code "111") (name "Net-(D85-Pad2)") (class "Default")
      (node (ref "D85") (pin "2") (pinfunction "2_2") (pintype "passive"))
      (node (ref "SW85") (pin "2") (pintype "passive"))
    )
    (net (code "112") (name "Net-(D86-Pad2)") (class "Default")
      (node (ref "D86") (pin "2") (pinfunction "2_2") (pintype "passive"))
      (node (ref "SW86") (pin "2") (pintype "passive"))
    )
    (net (code "113") (name "Net-(D87-Pad2)") (class "Default")
      (node (ref "D87") (pin "2") (pinfunction "2_2") (pintype "passive"))
      (node (ref "SW87") (pin "2") (pintype "passive"))
    )
    (net (code "114") (name "Net-(D88-Pad2)") (class "Default")
      (node (ref "D88") (pin "2") (pinfunction "2_2") (pintype "passive"))
      (node (ref "SW88") (pin "2") (pintype "passive"))
    )
    (net (code "115") (name "Net-(D89-Pad2)") (class "Default")
      (node (ref "D89") (pin "2") (pinfunction "2_2") (pintype "passive"))
      (node (ref "SW89") (pin "2") (pintype "passive"))
    )
    (net (code "116") (name "Net-(D90-Pad2)") (class "Default")
      (node (ref "D90") (pin "2") (pinfunction "2_2") (pintype "passive"))
      (node (ref "SW90") (pin "2") (pintype "passive"))
    )
    (net (code "117") (name "Net-(D91-Pad2)") (class "Default")
      (node (ref "D91") (pin "2") (pinfunction "2_2") (pintype "passive"))
      (node (ref "SW91") (pin "2") (pintype "passive"))
    )
    (net (code "118") (name "Net-(D92-Pad2)") (class "Default")
      (node (ref "D92") (pin "2") (pinfunction "2_2") (pintype "passive"))
      (node (ref "SW92") (pin "2") (pintype "passive"))
    )
    (net (code "119") (name "Net-(D93-Pad2)") (class "Default")
      (node (ref "D93") (pin "2") (pinfunction "2_2") (pintype "passive"))
      (node (ref "SW93") (pin "2") (pintype "passive"))
    )
    (net (code "120") (name "Net-(D94-Pad2)") (class "Default")
      (node (ref "D94") (pin "2") (pinfunction "2_2") (pintype "passive"))
      (node (ref "SW94") (pin "2") (pintype "passive"))
    )
    (net (code "121") (name "Net-(D95-Pad2)") (class "Default")
      (node (ref "D95") (pin "2") (pinfunction "2_2") (pintype "passive"))
      (node (ref "SW95") (pin "2") (pintype "passive"))
    )
    (net (code "122") (name "Net-(D96-Pad2)") (class "Default")
      (node (ref "D96") (pin "2") (pinfunction "2_2") (pintype "passive"))
      (node (ref "SW96") (pin "2") (pintype "passive"))
    )
    (net (code "123") (name "Net-(D97-Pad2)") (class "Default")
      (node (ref "D97") (pin "2") (pinfunction "2_2") (pintype "passive"))
      (node (ref "SW97") (pin "2") (pintype "passive"))
    )
    (net (code "124") (name "Net-(D98-Pad2)") (class "Default")
      (node (ref "D98") (pin "2") (pinfunction "2_2") (pintype "passive"))
      (node (ref "SW98") (pin "2") (pintype "passive"))
    )
    (net (code "125") (name "Net-(D99-Pad2)") (class "Default")
      (node (ref "D99") (pin "2") (pinfunction "2_2") (pintype "passive"))
      (node (ref "SW99") (pin "2") (pintype "passive"))
    )
    (net (code "126") (name "Net-(D100-Pad2)") (class "Default")
      (node (ref "D100") (pin "2") (pinfunction "2_2") (pintype "passive"))
      (node (ref "SW100") (pin "2") (pintype "passive"))
    )
    (net (code "127") (name "Net-(D101-Pad2)") (class "Default")
      (node (ref "D101") (pin "2") (pinfunction "2_2") (pintype "passive"))
      (node (ref "SW101") (pin "2") (pintype "passive"))
    )
    (net (code "128") (name "Net-(D102-Pad2)") (class "Default")
      (node (ref "D102") (pin "2") (pinfunction "2_2") (pintype "passive"))
      (node (ref "SW102") (pin "2") (pintype "passive"))
    )
    (net (code "129") (name "Net-(D103-Pad2)") (class "Default")
      (node (ref "D103") (pin "2") (pinfunction "2_2") (pintype "passive"))
      (node (ref "SW103") (pin "2") (pintype "passive"))
    )
    (net (code "130") (name "Net-(D104-Pad2)") (class "Default")
      (node (ref "D104") (pin "2") (pinfunction "2_2") (pintype "passive"))
      (node (ref "SW104") (pin "2") (pintype "passive"))
    )
    (net (code "131") (name "Net-(D105-Pad2)") (class "Default")
      (node (ref "D105") (pin "2") (pinfunction "2_2") (pintype "passive"))
      (node (ref "SW105") (pin "2") (pintype "passive"))
    )
    (net (code "132") (name "Net-(D106-Pad2)") (class "Default")
      (node (ref "D106") (pin "2") (pinfunction "2_2") (pintype "passive"))
      (node (ref "SW106") (pin "2") (pintype "passive"))
    )
  )
)
